# TopLevelDesign.net
KiCad netlist of a schematic drawn in Altium Designer
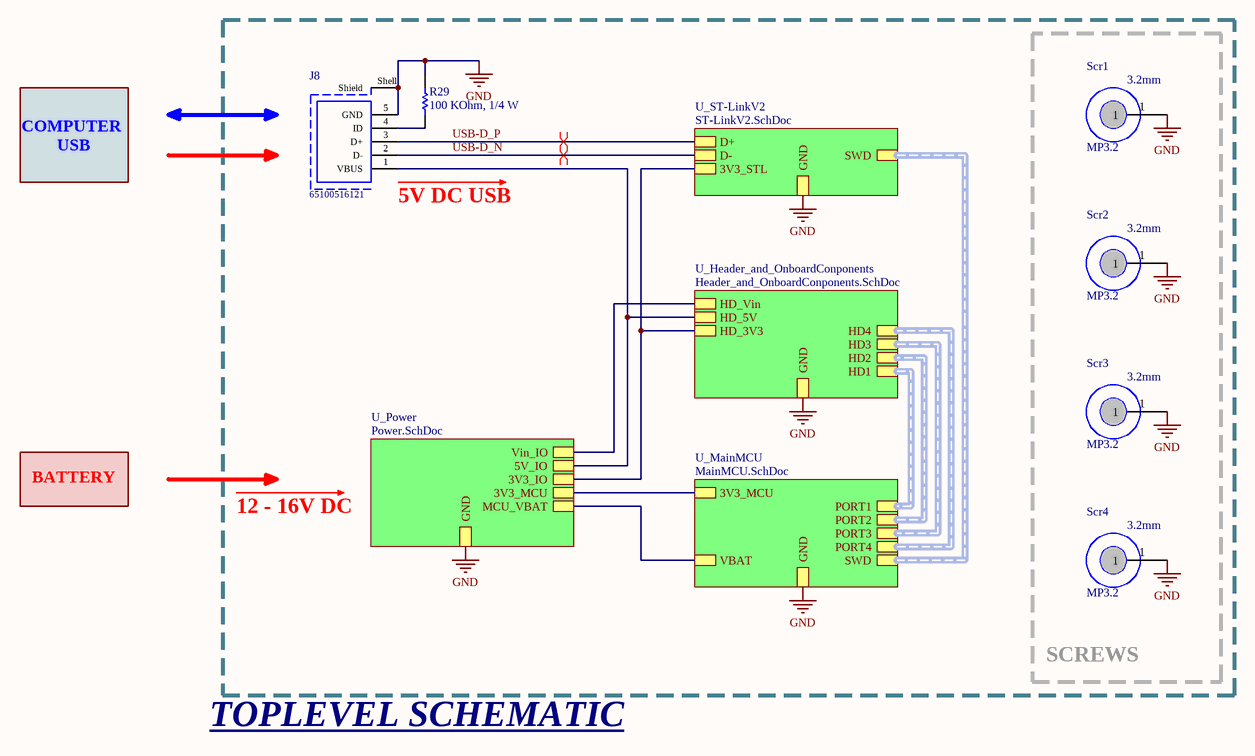
[diagram p0: TopLevelDesign.SchDoc]

(export (version "E")
  (design (tool "Eeschema 10.0.6"))
  (components
    (comp (ref "J8")
      (value "65100516121")
      (footprint "65100516121")
      (description "Mini USB 2.0 Type B Receptacle WR-COM, Horizontal, SMT, with Pads and Pegs")
      (fields (field (name "PUBLISHER") "Wurth Elektronik"))
      (libsource (lib "Tin Tran") (part "651305142821"))
    )
    (comp (ref "R29")
      (value "100 KOhm, 1/4 W")
      (footprint "resistor_0603")
      (description "RES, size 0603, 100 KOhm, 1/4 W")
      (fields (field (name "Comment") "0006031041"))
      (libsource (lib "Tin Tran") (part "00060371541"))
    )
    (comp (ref "Scr1") (value "MP3.2") (footprint "MP3.2") (libsource (lib "Tin Tran") (part "MP3.2")))
    (comp (ref "Scr2") (value "MP3.2") (footprint "MP3.2") (libsource (lib "Tin Tran") (part "MP3.2")))
    (comp (ref "Scr3") (value "MP3.2") (footprint "MP3.2") (libsource (lib "Tin Tran") (part "MP3.2")))
    (comp (ref "Scr4") (value "MP3.2") (footprint "MP3.2") (libsource (lib "Tin Tran") (part "MP3.2")))
  )
  (nets
    (net (code "3") (name "/5V_IO") (class "Default")
      (node (ref "J8") (pin "1") (pinfunction "VBUS_1") (pintype "passive"))
    )
    (net (code "11") (name "/USB-D_N") (class "Default")
      (node (ref "J8") (pin "2") (pinfunction "D-_2") (pintype "passive"))
    )
    (net (code "12") (name "/USB-D_P") (class "Default")
      (node (ref "J8") (pin "3") (pinfunction "D+_3") (pintype "passive"))
    )
    (net (code "13") (name "GND") (class "Default")
      (node (ref "J8") (pin "5") (pinfunction "GND_5") (pintype "passive"))
      (node (ref "J8") (pin "Shell") (pinfunction "Shield_Shell") (pintype "passive"))
      (node (ref "R29") (pin "2") (pinfunction "2_2") (pintype "passive"))
      (node (ref "Scr1") (pin "1") (pinfunction "1_1") (pintype "passive"))
      (node (ref "Scr2") (pin "1") (pinfunction "1_1") (pintype "passive"))
      (node (ref "Scr3") (pin "1") (pinfunction "1_1") (pintype "passive"))
      (node (ref "Scr4") (pin "1") (pinfunction "1_1") (pintype "passive"))
    )
    (net (code "14") (name "Net-(J8-ID)") (class "Default")
      (node (ref "J8") (pin "4") (pinfunction "ID_4") (pintype "passive"))
      (node (ref "R29") (pin "1") (pinfunction "1_1") (pintype "passive"))
    )
  )
)
